# TD_Toolboard_V2.net
KiCad netlist of a schematic drawn in EAGLE
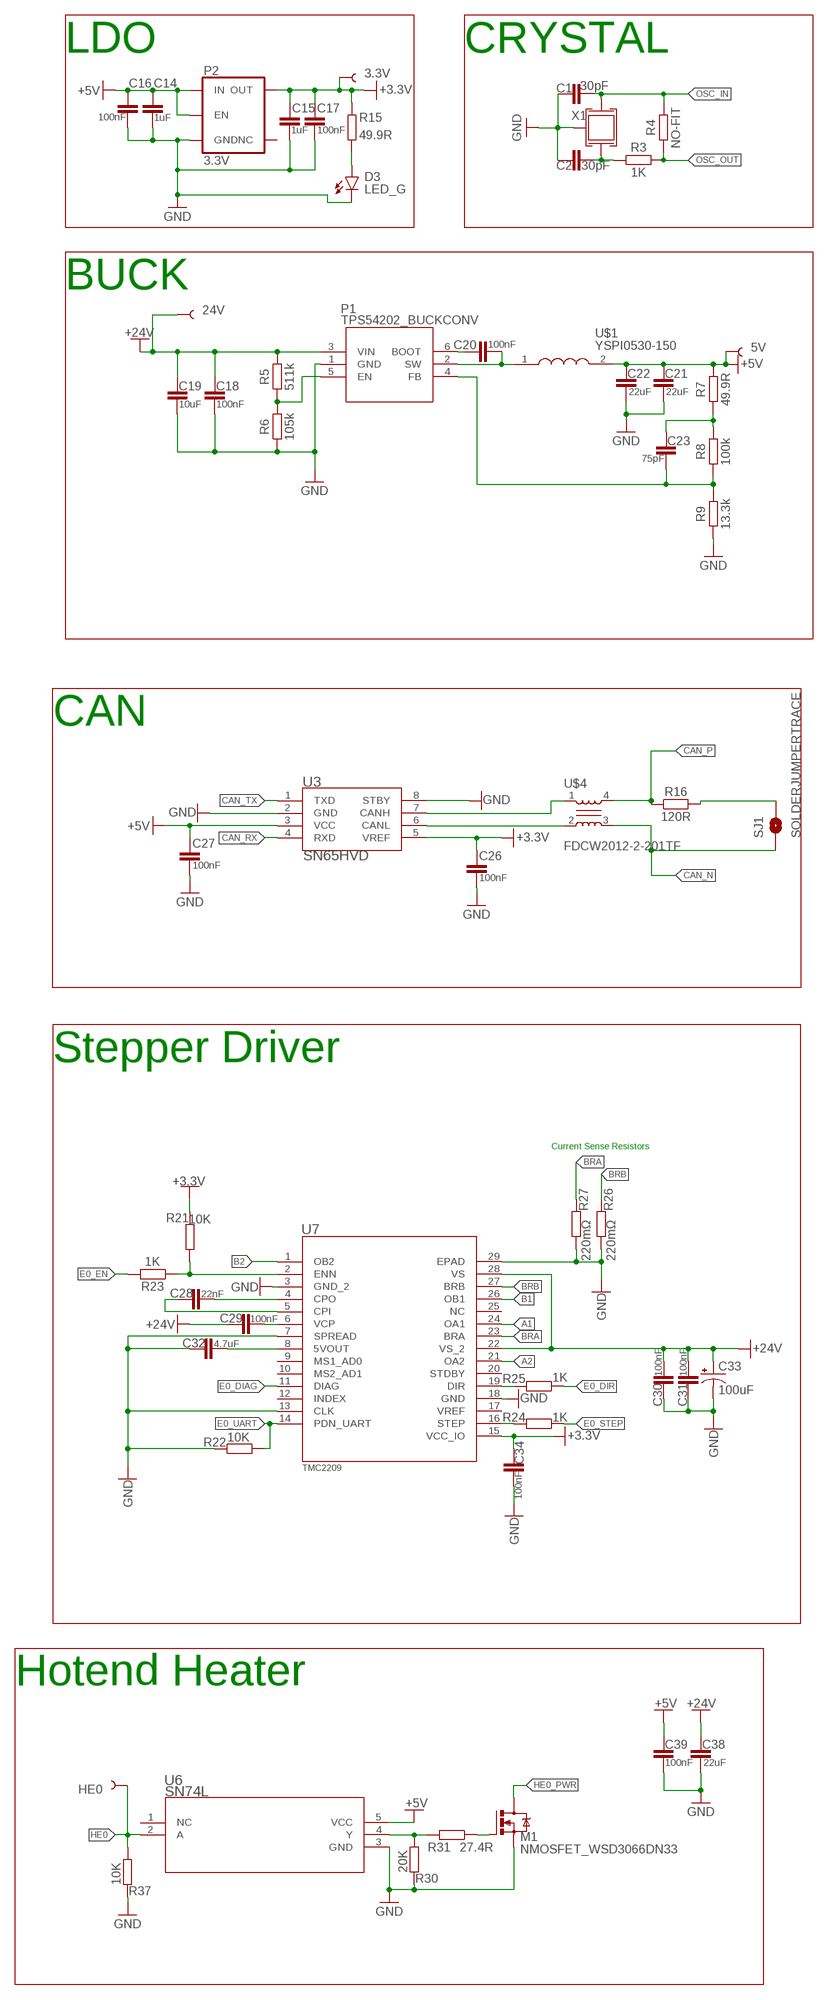
[diagram p0: schematic, sheet 1, part 1 of 2]
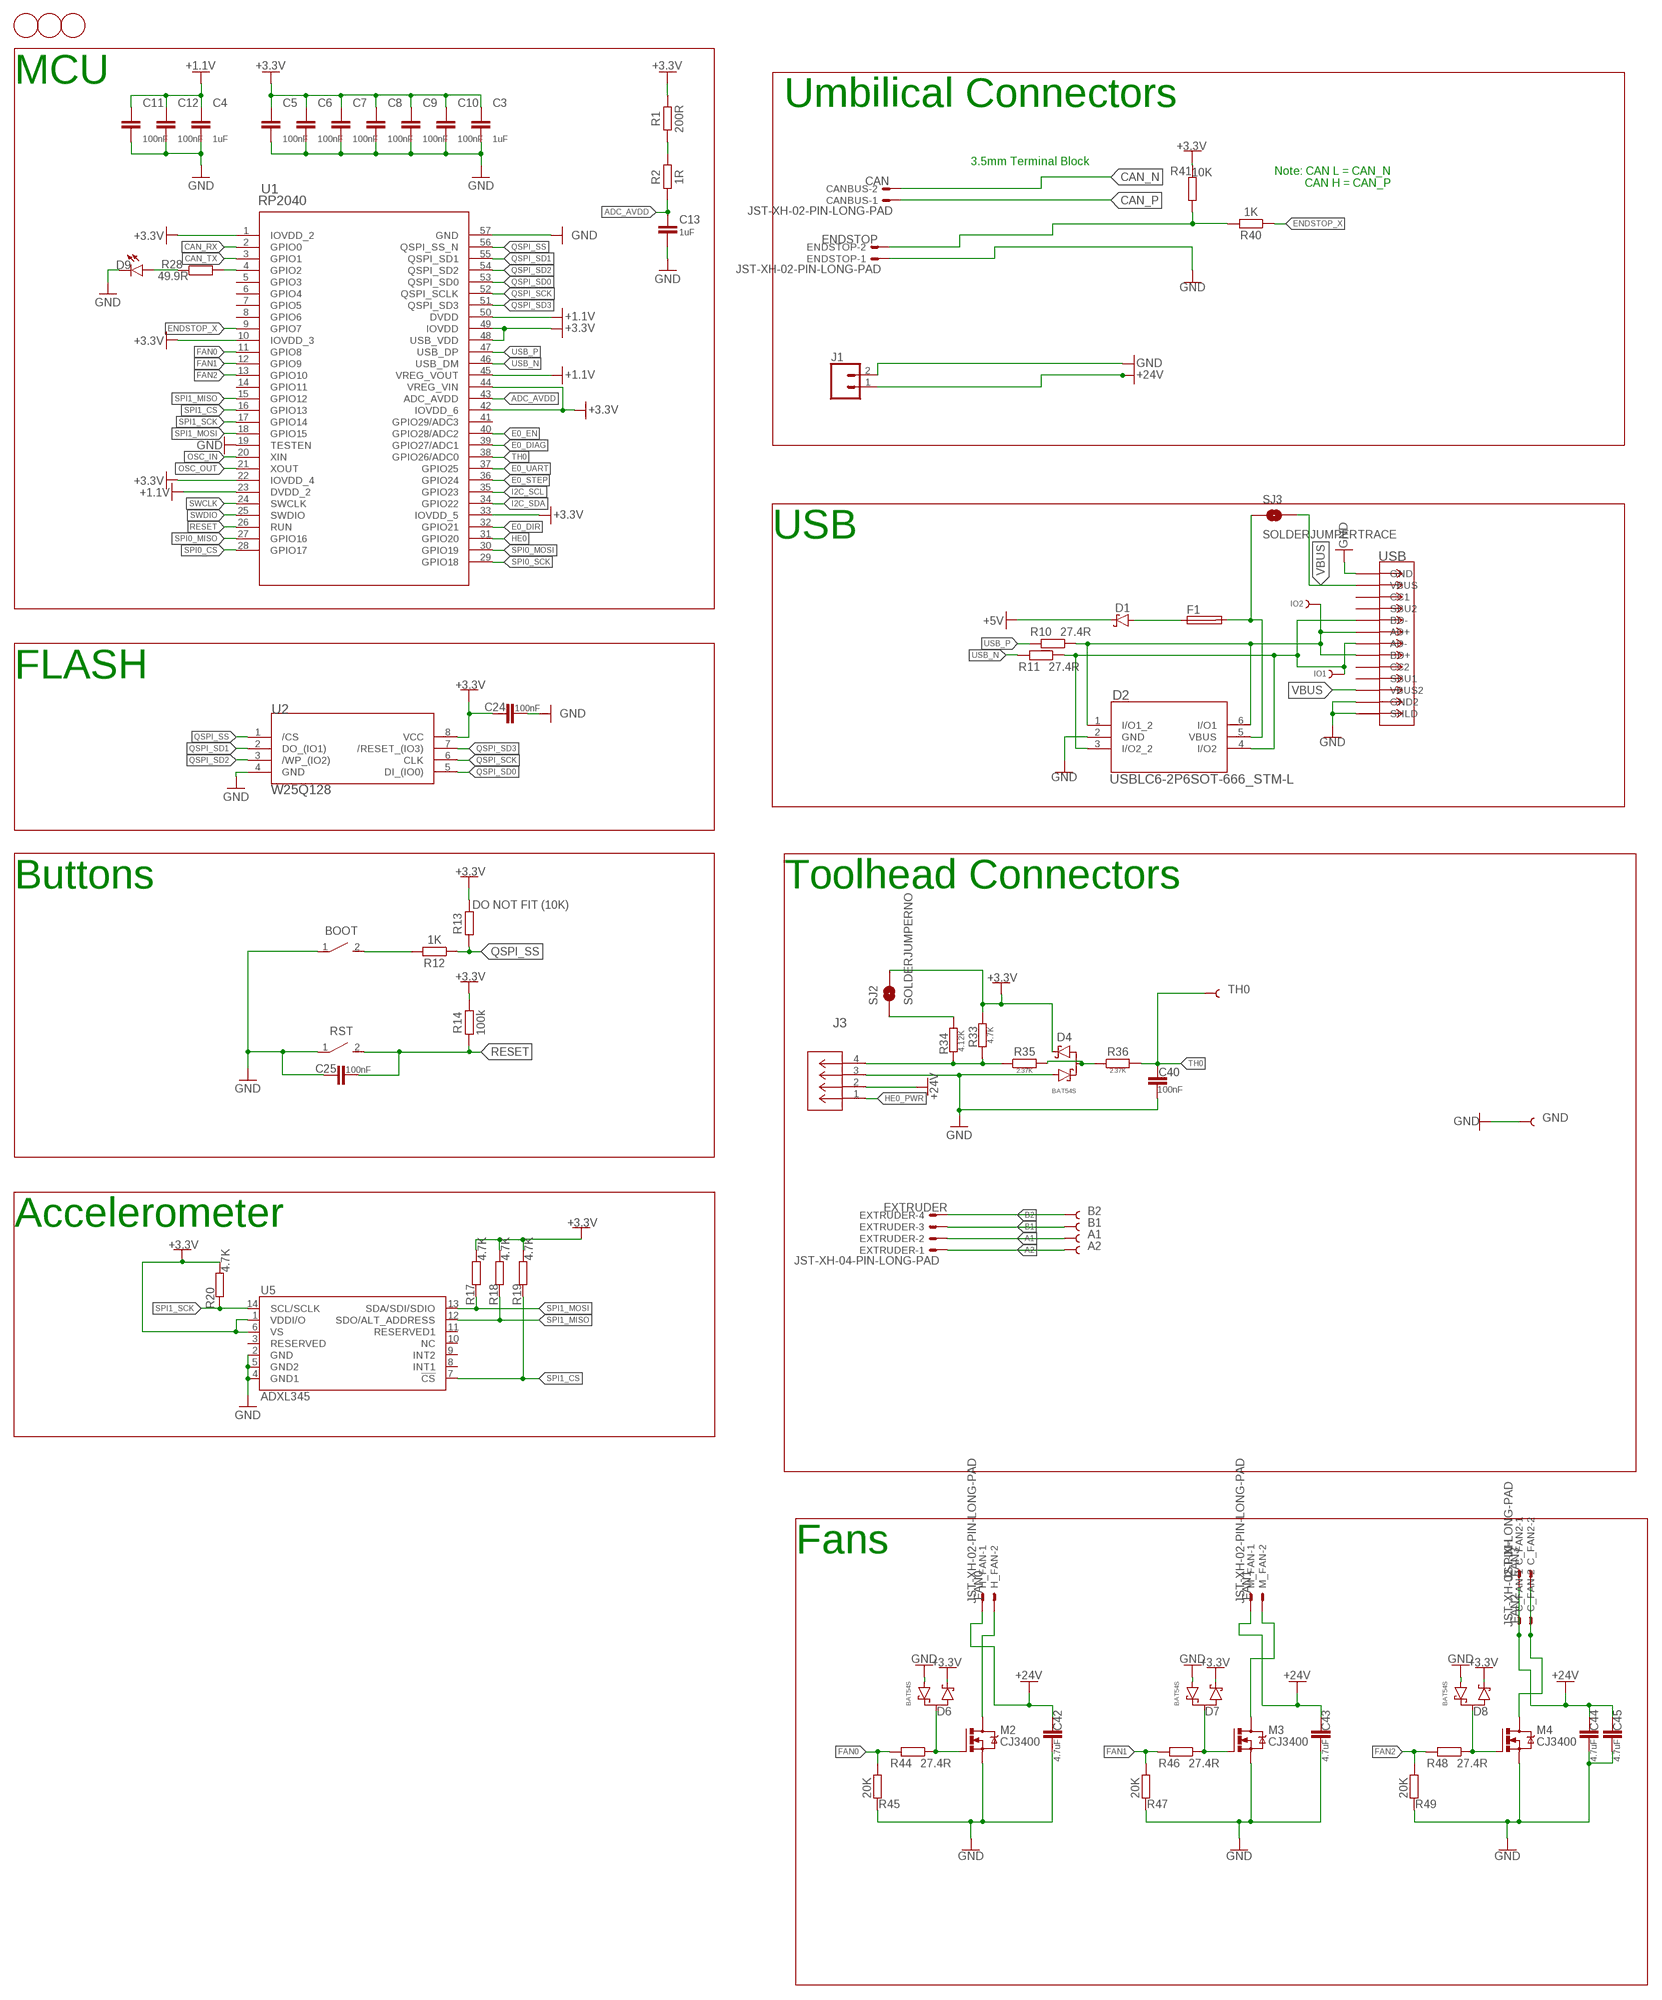
[diagram p1: schematic, sheet 1, part 2 of 2]

(export (version "E")
  (design (tool "Eeschema 10.0.6"))
  (components
    (comp (ref "3.3V")
      (value "TEST-POINT3X4")
      (footprint "eagle-import:PAD.03X.04")
      (libsource (lib "eagle-import") (part "TEST-POINT3X4"))
    )
    (comp (ref "5V")
      (value "TEST-POINT3X4")
      (footprint "eagle-import:PAD.03X.04")
      (libsource (lib "eagle-import") (part "TEST-POINT3X4"))
    )
    (comp (ref "24V")
      (value "TEST-POINT3X4")
      (footprint "eagle-import:PAD.03X.04")
      (libsource (lib "eagle-import") (part "TEST-POINT3X4"))
    )
    (comp (ref "A1")
      (value "TEST-POINT3X4")
      (footprint "eagle-import:PAD.03X.04")
      (libsource (lib "eagle-import") (part "TEST-POINT3X4"))
    )
    (comp (ref "A2")
      (value "TEST-POINT3X4")
      (footprint "eagle-import:PAD.03X.04")
      (libsource (lib "eagle-import") (part "TEST-POINT3X4"))
    )
    (comp (ref "B1")
      (value "TEST-POINT3X4")
      (footprint "eagle-import:PAD.03X.04")
      (libsource (lib "eagle-import") (part "TEST-POINT3X4"))
    )
    (comp (ref "B2")
      (value "TEST-POINT3X4")
      (footprint "eagle-import:PAD.03X.04")
      (libsource (lib "eagle-import") (part "TEST-POINT3X4"))
    )
    (comp (ref "BOOT")
      (value "B3U-1000P(M)-B")
      (footprint "eagle-import:B3U-1000P(M)-B")
      (fields (field (name "MANUFACTURER") "OMRON"))
      (libsource (lib "eagle-import") (part "B3U-X0001000P(M)-BB3U-1000P(M)-B"))
    )
    (comp (ref "C1")
      (value "30pF")
      (footprint "eagle-import:CAPC1005X60")
      (libsource (lib "eagle-import") (part "CCHIP-0402(1005-METRIC)_"))
    )
    (comp (ref "C2")
      (value "30pF")
      (footprint "eagle-import:CAPC1005X60")
      (libsource (lib "eagle-import") (part "CCHIP-0402(1005-METRIC)_"))
    )
    (comp (ref "C3")
      (value "1uF")
      (footprint "eagle-import:CAPC1005X60")
      (libsource (lib "eagle-import") (part "CCHIP-0402(1005-METRIC)_"))
    )
    (comp (ref "C4")
      (value "1uF")
      (footprint "eagle-import:CAPC1005X60")
      (libsource (lib "eagle-import") (part "CCHIP-0402(1005-METRIC)_"))
    )
    (comp (ref "C5")
      (value "100nF")
      (footprint "eagle-import:CAPC1005X60")
      (libsource (lib "eagle-import") (part "CCHIP-0402(1005-METRIC)_"))
    )
    (comp (ref "C6")
      (value "100nF")
      (footprint "eagle-import:CAPC1005X60")
      (libsource (lib "eagle-import") (part "CCHIP-0402(1005-METRIC)_"))
    )
    (comp (ref "C7")
      (value "100nF")
      (footprint "eagle-import:CAPC1005X60")
      (libsource (lib "eagle-import") (part "CCHIP-0402(1005-METRIC)_"))
    )
    (comp (ref "C8")
      (value "100nF")
      (footprint "eagle-import:CAPC1005X60")
      (libsource (lib "eagle-import") (part "CCHIP-0402(1005-METRIC)_"))
    )
    (comp (ref "C9")
      (value "100nF")
      (footprint "eagle-import:CAPC1005X60")
      (libsource (lib "eagle-import") (part "CCHIP-0402(1005-METRIC)_"))
    )
    (comp (ref "C10")
      (value "100nF")
      (footprint "eagle-import:CAPC1005X60")
      (libsource (lib "eagle-import") (part "CCHIP-0402(1005-METRIC)_"))
    )
    (comp (ref "C11")
      (value "100nF")
      (footprint "eagle-import:CAPC1005X60")
      (libsource (lib "eagle-import") (part "CCHIP-0402(1005-METRIC)_"))
    )
    (comp (ref "C12")
      (value "100nF")
      (footprint "eagle-import:CAPC1005X60")
      (libsource (lib "eagle-import") (part "CCHIP-0402(1005-METRIC)_"))
    )
    (comp (ref "C13")
      (value "1uF")
      (footprint "eagle-import:CAPC1005X60")
      (libsource (lib "eagle-import") (part "CCHIP-0402(1005-METRIC)_"))
    )
    (comp (ref "C14")
      (value "1uF")
      (footprint "eagle-import:CAPC1005X60")
      (libsource (lib "eagle-import") (part "CCHIP-0402(1005-METRIC)_"))
    )
    (comp (ref "C15")
      (value "1uF")
      (footprint "eagle-import:CAPC1005X60")
      (libsource (lib "eagle-import") (part "CCHIP-0402(1005-METRIC)_"))
    )
    (comp (ref "C16")
      (value "100nF")
      (footprint "eagle-import:CAPC1005X60")
      (libsource (lib "eagle-import") (part "CCHIP-0402(1005-METRIC)_"))
    )
    (comp (ref "C17")
      (value "100nF")
      (footprint "eagle-import:CAPC1005X60")
      (libsource (lib "eagle-import") (part "CCHIP-0402(1005-METRIC)_"))
    )
    (comp (ref "C18")
      (value "100nF")
      (footprint "eagle-import:CAPC1005X60")
      (libsource (lib "eagle-import") (part "CCHIP-0402(1005-METRIC)_"))
    )
    (comp (ref "C19")
      (value "10uF")
      (footprint "eagle-import:CAPC1608X85")
      (libsource (lib "eagle-import") (part "CCHIP-0603(1608-METRIC)_"))
    )
    (comp (ref "C20")
      (value "100nF")
      (footprint "eagle-import:CAPC1005X60")
      (libsource (lib "eagle-import") (part "CCHIP-0402(1005-METRIC)_"))
    )
    (comp (ref "C21")
      (value "22uF")
      (footprint "eagle-import:CAPC2012X110")
      (libsource (lib "eagle-import") (part "CCHIP-0805(2012-METRIC)_"))
    )
    (comp (ref "C22")
      (value "22uF")
      (footprint "eagle-import:CAPC2012X110")
      (libsource (lib "eagle-import") (part "CCHIP-0805(2012-METRIC)_"))
    )
    (comp (ref "C23")
      (value "75pF")
      (footprint "eagle-import:CAPC1005X60")
      (libsource (lib "eagle-import") (part "CCHIP-0402(1005-METRIC)_"))
    )
    (comp (ref "C24")
      (value "100nF")
      (footprint "eagle-import:CAPC1005X60")
      (libsource (lib "eagle-import") (part "CCHIP-0402(1005-METRIC)_"))
    )
    (comp (ref "C25")
      (value "100nF")
      (footprint "eagle-import:CAPC1005X60")
      (libsource (lib "eagle-import") (part "CCHIP-0402(1005-METRIC)_"))
    )
    (comp (ref "C26")
      (value "100nF")
      (footprint "eagle-import:CAPC1005X60")
      (libsource (lib "eagle-import") (part "CCHIP-0402(1005-METRIC)_"))
    )
    (comp (ref "C27")
      (value "100nF")
      (footprint "eagle-import:CAPC1005X60")
      (libsource (lib "eagle-import") (part "CCHIP-0402(1005-METRIC)_"))
    )
    (comp (ref "C28")
      (value "22nF")
      (footprint "eagle-import:CAPC1005X60")
      (libsource (lib "eagle-import") (part "CCHIP-0402(1005-METRIC)_"))
    )
    (comp (ref "C29")
      (value "100nF")
      (footprint "eagle-import:CAPC1005X60")
      (libsource (lib "eagle-import") (part "CCHIP-0402(1005-METRIC)_"))
    )
    (comp (ref "C30")
      (value "100nF")
      (footprint "eagle-import:CAPC1005X60")
      (libsource (lib "eagle-import") (part "CCHIP-0402(1005-METRIC)_"))
    )
    (comp (ref "C31")
      (value "100nF")
      (footprint "eagle-import:CAPC1005X60")
      (libsource (lib "eagle-import") (part "CCHIP-0402(1005-METRIC)_"))
    )
    (comp (ref "C32")
      (value "4.7uF")
      (footprint "eagle-import:CAPC1608X85")
      (libsource (lib "eagle-import") (part "CCHIP-0603(1608-METRIC)_"))
    )
    (comp (ref "C33")
      (value "100uF")
      (footprint "eagle-import:PANASONIC_D")
      (libsource (lib "eagle-import") (part "100UF-POLAR-25V-20%(ELEC)"))
    )
    (comp (ref "C34")
      (value "100nF")
      (footprint "eagle-import:CAPC1005X60")
      (libsource (lib "eagle-import") (part "CCHIP-0402(1005-METRIC)_"))
    )
    (comp (ref "C38")
      (value "22uF")
      (footprint "eagle-import:CAPC2012X110")
      (libsource (lib "eagle-import") (part "CCHIP-0805(2012-METRIC)_"))
    )
    (comp (ref "C39")
      (value "100nF")
      (footprint "eagle-import:CAPC1005X60")
      (libsource (lib "eagle-import") (part "CCHIP-0402(1005-METRIC)_"))
    )
    (comp (ref "C40")
      (value "100nF")
      (footprint "eagle-import:CAPC1005X60")
      (libsource (lib "eagle-import") (part "CCHIP-0402(1005-METRIC)_"))
    )
    (comp (ref "C42")
      (value "4.7uF")
      (footprint "eagle-import:CAPC1608X85")
      (libsource (lib "eagle-import") (part "CCHIP-0603(1608-METRIC)_"))
    )
    (comp (ref "C43")
      (value "4.7uF")
      (footprint "eagle-import:CAPC1608X85")
      (libsource (lib "eagle-import") (part "CCHIP-0603(1608-METRIC)_"))
    )
    (comp (ref "C44")
      (value "4.7uF")
      (footprint "eagle-import:CAPC1608X85")
      (libsource (lib "eagle-import") (part "CCHIP-0603(1608-METRIC)_"))
    )
    (comp (ref "C45")
      (value "4.7uF")
      (footprint "eagle-import:CAPC1608X85")
      (libsource (lib "eagle-import") (part "CCHIP-0603(1608-METRIC)_"))
    )
    (comp (ref "CANBUS")
      (value "JST-XH-02-PIN-LONG-PAD")
      (footprint "eagle-import:JST-XH-02-PACKAGE-LONG-PAD")
      (libsource (lib "eagle-import") (part "JST-XH-02-PIN-LONG-PAD"))
    )
    (comp (ref "C_FAN")
      (value "JST-XH-02-PIN-LONG-PAD")
      (footprint "eagle-import:JST-XH-02-PACKAGE-LONG-PAD")
      (libsource (lib "eagle-import") (part "JST-XH-02-PIN-LONG-PAD"))
    )
    (comp (ref "C_FAN2")
      (value "JST-XH")
      (footprint "eagle-import:JST-XH-02-PACKAGE-LONG-PAD")
      (libsource (lib "eagle-import") (part "JST-XH-02-PIN-LONG-PAD"))
    )
    (comp (ref "D1")
      (value "MBR0520LT1G")
      (footprint "eagle-import:SODFL3718X115")
      (fields (field (name "MANUFACTURER") "ON Semiconductor"))
      (libsource (lib "eagle-import") (part "SCHOTTKY_DO-219MBR0520LT1G"))
    )
    (comp (ref "D2")
      (value "USBLC6-2P6SOT-666_STM-L")
      (footprint "eagle-import:SOT-666_STM-L")
      (fields
        (field (name "MANUFACTURER_PART_NUMBER") "USBLC6-2P6")
        (field (name "COPYRIGHT") "Copyright (C) 2023 Ultra Librarian. All rights reserved.")
      )
      (libsource (lib "eagle-import") (part "USBLC6-2P6SOT-666_STM-L"))
    )
    (comp (ref "D3")
      (value "LED_G")
      (footprint "eagle-import:LEDC1608X35N_FLAT-G")
      (libsource (lib "eagle-import") (part "CHIP-FLAT-G_0603-0.35MM"))
    )
    (comp (ref "D4")
      (value "BAT54S")
      (footprint "eagle-import:SOT23")
      (libsource (lib "eagle-import") (part "BAT54S"))
    )
    (comp (ref "D6")
      (value "BAT54S")
      (footprint "eagle-import:SOT23")
      (libsource (lib "eagle-import") (part "BAT54S"))
    )
    (comp (ref "D7")
      (value "BAT54S")
      (footprint "eagle-import:SOT23")
      (libsource (lib "eagle-import") (part "BAT54S"))
    )
    (comp (ref "D8")
      (value "BAT54S")
      (footprint "eagle-import:SOT23")
      (libsource (lib "eagle-import") (part "BAT54S"))
    )
    (comp (ref "D9")
      (value "LED_G")
      (footprint "eagle-import:LED3MM")
      (libsource (lib "eagle-import") (part "LED3MM"))
    )
    (comp (ref "ENDSTOP")
      (value "JST-XH-02-PIN-LONG-PAD")
      (footprint "eagle-import:JST-XH-02-PACKAGE-LONG-PAD")
      (libsource (lib "eagle-import") (part "JST-XH-02-PIN-LONG-PAD"))
    )
    (comp (ref "EXTRUDER")
      (value "JST-XH-04-PIN-LONG-PAD")
      (footprint "eagle-import:JST-XH-04-PACKAGE-LONG-PAD")
      (libsource (lib "eagle-import") (part "JST-XH-04-PIN-LONG-PAD"))
    )
    (comp (ref "F1")
      (value "FUSE_CHIP-0603(1608-METRIC)")
      (footprint "eagle-import:FUSC1608X60N")
      (libsource (lib "eagle-import") (part "FUSECHIP-0603(1608-METRIC)_"))
    )
    (comp (ref "FD4")
      (value "FIDUCIAL")
      (footprint "eagle-import:FIDUCIAL_1MM")
      (libsource (lib "eagle-import") (part "FIDUCIAL"))
    )
    (comp (ref "FD5")
      (value "FIDUCIAL")
      (footprint "eagle-import:FIDUCIAL_1MM")
      (libsource (lib "eagle-import") (part "FIDUCIAL"))
    )
    (comp (ref "FD6")
      (value "FIDUCIAL")
      (footprint "eagle-import:FIDUCIAL_1MM")
      (libsource (lib "eagle-import") (part "FIDUCIAL"))
    )
    (comp (ref "GND")
      (value "TEST-POINT3X4")
      (footprint "eagle-import:PAD.03X.04")
      (libsource (lib "eagle-import") (part "TEST-POINT3X4"))
    )
    (comp (ref "HE0")
      (value "TEST-POINT3X4")
      (footprint "eagle-import:PAD.03X.04")
      (libsource (lib "eagle-import") (part "TEST-POINT3X4"))
    )
    (comp (ref "H_FAN")
      (value "JST-XH-02-PIN-LONG-PAD")
      (footprint "eagle-import:JST-XH-02-PACKAGE-LONG-PAD")
      (libsource (lib "eagle-import") (part "JST-XH-02-PIN-LONG-PAD"))
    )
    (comp (ref "IO1")
      (value "TEST-POINT3")
      (footprint "eagle-import:PAD.03X.03")
      (libsource (lib "eagle-import") (part "TEST-POINT3"))
    )
    (comp (ref "IO2")
      (value "TEST-POINT3")
      (footprint "eagle-import:PAD.03X.03")
      (libsource (lib "eagle-import") (part "TEST-POINT3"))
    )
    (comp (ref "J1")
      (value "CONN_023.5MM")
      (footprint "eagle-import:SCREWTERMINAL-3.5MM-2")
      (libsource (lib "eagle-import") (part "CONN_023.5MM"))
    )
    (comp (ref "J3")
      (value "JST-MICROFIT")
      (footprint "eagle-import:CON_430450400_MOL")
      (fields
        (field (name "MANUFACTURER_PART_NUMBER") "430450400")
        (field (name "COPYRIGHT") "Copyright (C) 2023 Ultra Librarian. All rights reserved.")
      )
      (libsource (lib "eagle-import") (part "430450400CON_430450400_MOL"))
    )
    (comp (ref "M1")
      (value "NMOSFET_WSD3066DN33")
      (footprint "eagle-import:NMOSFET_WSD3066DN33")
      (libsource (lib "eagle-import") (part "NMOSFET_WSD3066DN33"))
    )
    (comp (ref "M2")
      (value "CJ3400")
      (footprint "eagle-import:SOT23")
      (fields (field (name "MANUFACTURER") "ON Semiconductor") (field (name "MPN") "BSS123L"))
      (libsource (lib "eagle-import") (part "NMOSFET__SOT23-GSDBSS123"))
    )
    (comp (ref "M3")
      (value "CJ3400")
      (footprint "eagle-import:SOT23")
      (fields (field (name "MANUFACTURER") "ON Semiconductor") (field (name "MPN") "BSS123L"))
      (libsource (lib "eagle-import") (part "NMOSFET__SOT23-GSDBSS123"))
    )
    (comp (ref "M4")
      (value "CJ3400")
      (footprint "eagle-import:SOT23")
      (fields (field (name "MANUFACTURER") "ON Semiconductor") (field (name "MPN") "BSS123L"))
      (libsource (lib "eagle-import") (part "NMOSFET__SOT23-GSDBSS123"))
    )
    (comp (ref "M_FAN")
      (value "JST-XH-02-PIN-LONG-PAD")
      (footprint "eagle-import:JST-XH-02-PACKAGE-LONG-PAD")
      (libsource (lib "eagle-import") (part "JST-XH-02-PIN-LONG-PAD"))
    )
    (comp (ref "P1")
      (value "TPS54202_BUCKCONV")
      (footprint "eagle-import:SOT-23-6")
      (libsource (lib "eagle-import") (part "TPS54202_BUCKCONV"))
    )
    (comp (ref "P2")
      (value "3.3V")
      (footprint "eagle-import:SOT23-5")
      (libsource (lib "eagle-import") (part "V_REG_AP2112K-3.3V"))
    )
    (comp (ref "R1")
      (value "200R")
      (footprint "eagle-import:RESC1005X40")
      (libsource (lib "eagle-import") (part "RCHIP-0402(1005-METRIC)_"))
    )
    (comp (ref "R2")
      (value "1R")
      (footprint "eagle-import:RESC1005X40")
      (libsource (lib "eagle-import") (part "RCHIP-0402(1005-METRIC)_"))
    )
    (comp (ref "R3")
      (value "1K")
      (footprint "eagle-import:RESC1005X40")
      (libsource (lib "eagle-import") (part "RCHIP-0402(1005-METRIC)_"))
    )
    (comp (ref "R4")
      (value "NO-FIT")
      (footprint "eagle-import:RESC1005X40")
      (libsource (lib "eagle-import") (part "RCHIP-0402(1005-METRIC)_"))
    )
    (comp (ref "R5")
      (value "511k")
      (footprint "eagle-import:RESC1005X40")
      (libsource (lib "eagle-import") (part "RCHIP-0402(1005-METRIC)_"))
    )
    (comp (ref "R6")
      (value "105k")
      (footprint "eagle-import:RESC1005X40")
      (libsource (lib "eagle-import") (part "RCHIP-0402(1005-METRIC)_"))
    )
    (comp (ref "R7")
      (value "49.9R")
      (footprint "eagle-import:RESC1005X40")
      (libsource (lib "eagle-import") (part "RCHIP-0402(1005-METRIC)_"))
    )
    (comp (ref "R8")
      (value "100k")
      (footprint "eagle-import:RESC1005X40")
      (libsource (lib "eagle-import") (part "RCHIP-0402(1005-METRIC)_"))
    )
    (comp (ref "R9")
      (value "13.3k")
      (footprint "eagle-import:RESC1005X40")
      (libsource (lib "eagle-import") (part "RCHIP-0402(1005-METRIC)_"))
    )
    (comp (ref "R10")
      (value "27.4R")
      (footprint "eagle-import:RESC1005X40")
      (libsource (lib "eagle-import") (part "RCHIP-0402(1005-METRIC)_"))
    )
    (comp (ref "R11")
      (value "27.4R")
      (footprint "eagle-import:RESC1005X40")
      (libsource (lib "eagle-import") (part "RCHIP-0402(1005-METRIC)_"))
    )
    (comp (ref "R12")
      (value "1K")
      (footprint "eagle-import:RESC1005X40")
      (libsource (lib "eagle-import") (part "RCHIP-0402(1005-METRIC)_"))
    )
    (comp (ref "R13")
      (value "DO NOT FIT (10K)")
      (footprint "eagle-import:RESC1005X40")
      (libsource (lib "eagle-import") (part "RCHIP-0402(1005-METRIC)_"))
    )
    (comp (ref "R14")
      (value "100k")
      (footprint "eagle-import:RESC1005X40")
      (libsource (lib "eagle-import") (part "RCHIP-0402(1005-METRIC)_"))
    )
    (comp (ref "R15")
      (value "49.9R")
      (footprint "eagle-import:RESC1005X40")
      (libsource (lib "eagle-import") (part "RCHIP-0402(1005-METRIC)_"))
    )
    (comp (ref "R16")
      (value "120R")
      (footprint "eagle-import:RESC1005X40")
      (libsource (lib "eagle-import") (part "RCHIP-0402(1005-METRIC)_"))
    )
    (comp (ref "R17")
      (value "4.7K")
      (footprint "eagle-import:RESC1005X40")
      (libsource (lib "eagle-import") (part "RCHIP-0402(1005-METRIC)_"))
    )
    (comp (ref "R18")
      (value "4.7K")
      (footprint "eagle-import:RESC1005X40")
      (libsource (lib "eagle-import") (part "RCHIP-0402(1005-METRIC)_"))
    )
    (comp (ref "R19")
      (value "4.7K")
      (footprint "eagle-import:RESC1005X40")
      (libsource (lib "eagle-import") (part "RCHIP-0402(1005-METRIC)_"))
    )
    (comp (ref "R20")
      (value "4.7K")
      (footprint "eagle-import:RESC1005X40")
      (libsource (lib "eagle-import") (part "RCHIP-0402(1005-METRIC)_"))
    )
    (comp (ref "R21")
      (value "10K")
      (footprint "eagle-import:RESC1005X40")
      (libsource (lib "eagle-import") (part "RCHIP-0402(1005-METRIC)_"))
    )
    (comp (ref "R22")
      (value "10K")
      (footprint "eagle-import:RESC1005X40")
      (libsource (lib "eagle-import") (part "RCHIP-0402(1005-METRIC)_"))
    )
    (comp (ref "R23")
      (value "1K")
      (footprint "eagle-import:RESC1005X40")
      (libsource (lib "eagle-import") (part "RCHIP-0402(1005-METRIC)_"))
    )
    (comp (ref "R24")
      (value "1K")
      (footprint "eagle-import:RESC1005X40")
      (libsource (lib "eagle-import") (part "RCHIP-0402(1005-METRIC)_"))
    )
    (comp (ref "R25")
      (value "1K")
      (footprint "eagle-import:RESC1005X40")
      (libsource (lib "eagle-import") (part "RCHIP-0402(1005-METRIC)_"))
    )
    (comp (ref "R26")
      (value "220mΩ")
      (footprint "eagle-import:RESC1005X40")
      (libsource (lib "eagle-import") (part "RCHIP-0402(1005-METRIC)_"))
    )
    (comp (ref "R27")
      (value "220mΩ")
      (footprint "eagle-import:RESC1005X40")
      (libsource (lib "eagle-import") (part "RCHIP-0402(1005-METRIC)_"))
    )
    (comp (ref "R28")
      (value "49.9R")
      (footprint "eagle-import:RESC1005X40")
      (libsource (lib "eagle-import") (part "RCHIP-0402(1005-METRIC)_"))
    )
    (comp (ref "R30")
      (value "20K")
      (footprint "eagle-import:RESC1005X40")
      (libsource (lib "eagle-import") (part "RCHIP-0402(1005-METRIC)_"))
    )
    (comp (ref "R31")
      (value "27.4R")
      (footprint "eagle-import:RESC1005X40")
      (libsource (lib "eagle-import") (part "RCHIP-0402(1005-METRIC)_"))
    )
    (comp (ref "R33")
      (value "4.7K")
      (footprint "eagle-import:RESC1005X40")
      (libsource (lib "eagle-import") (part "RCHIP-0402(1005-METRIC)_"))
    )
    (comp (ref "R34")
      (value "4.12K")
      (footprint "eagle-import:RESC1005X40")
      (libsource (lib "eagle-import") (part "RCHIP-0402(1005-METRIC)_"))
    )
    (comp (ref "R35")
      (value "2.37K")
      (footprint "eagle-import:RESC1005X40")
      (libsource (lib "eagle-import") (part "RCHIP-0402(1005-METRIC)_"))
    )
    (comp (ref "R36")
      (value "2.37K")
      (footprint "eagle-import:RESC1005X40")
      (libsource (lib "eagle-import") (part "RCHIP-0402(1005-METRIC)_"))
    )
    (comp (ref "R37")
      (value "10K")
      (footprint "eagle-import:RESC1005X40")
      (libsource (lib "eagle-import") (part "RCHIP-0402(1005-METRIC)_"))
    )
    (comp (ref "R40")
      (value "1K")
      (footprint "eagle-import:RESC1005X40")
      (libsource (lib "eagle-import") (part "RCHIP-0402(1005-METRIC)_"))
    )
    (comp (ref "R41")
      (value "10K")
      (footprint "eagle-import:RESC1005X40")
      (libsource (lib "eagle-import") (part "RCHIP-0402(1005-METRIC)_"))
    )
    (comp (ref "R44")
      (value "27.4R")
      (footprint "eagle-import:RESC1005X40")
      (libsource (lib "eagle-import") (part "RCHIP-0402(1005-METRIC)_"))
    )
    (comp (ref "R45")
      (value "20K")
      (footprint "eagle-import:RESC1005X40")
      (libsource (lib "eagle-import") (part "RCHIP-0402(1005-METRIC)_"))
    )
    (comp (ref "R46")
      (value "27.4R")
      (footprint "eagle-import:RESC1005X40")
      (libsource (lib "eagle-import") (part "RCHIP-0402(1005-METRIC)_"))
    )
    (comp (ref "R47")
      (value "20K")
      (footprint "eagle-import:RESC1005X40")
      (libsource (lib "eagle-import") (part "RCHIP-0402(1005-METRIC)_"))
    )
    (comp (ref "R48")
      (value "27.4R")
      (footprint "eagle-import:RESC1005X40")
      (libsource (lib "eagle-import") (part "RCHIP-0402(1005-METRIC)_"))
    )
    (comp (ref "R49")
      (value "20K")
      (footprint "eagle-import:RESC1005X40")
      (libsource (lib "eagle-import") (part "RCHIP-0402(1005-METRIC)_"))
    )
    (comp (ref "RST")
      (value "B3U-1000P(M)-B")
      (footprint "eagle-import:B3U-1000P(M)-B")
      (fields (field (name "MANUFACTURER") "OMRON"))
      (libsource (lib "eagle-import") (part "B3U-X0001000P(M)-BB3U-1000P(M)-B"))
    )
    (comp (ref "SJ1")
      (value "SOLDERJUMPERTRACE")
      (footprint "eagle-import:SJ_2S-TRACE")
      (libsource (lib "eagle-import") (part "SOLDERJUMPERTRACE"))
    )
    (comp (ref "SJ2")
      (value "SOLDERJUMPERNO")
      (footprint "eagle-import:SJ_2S-NO")
      (libsource (lib "eagle-import") (part "SOLDERJUMPERNO"))
    )
    (comp (ref "SJ3")
      (value "SOLDERJUMPERTRACE")
      (footprint "eagle-import:SJ_2S-TRACE")
      (libsource (lib "eagle-import") (part "SOLDERJUMPERTRACE"))
    )
    (comp (ref "TH0")
      (value "TEST-POINT3X4")
      (footprint "eagle-import:PAD.03X.04")
      (libsource (lib "eagle-import") (part "TEST-POINT3X4"))
    )
    (comp (ref "U$1")
      (value "YSPI0530-150")
      (footprint "eagle-import:YSPI0530-150")
      (libsource (lib "eagle-import") (part "YSPI0530-150"))
    )
    (comp (ref "U$4")
      (value "FDCW2012-2-201TF")
      (footprint "eagle-import:FDCW2012-2-201TF")
      (libsource (lib "eagle-import") (part "FDCW2012-2-201TF"))
    )
    (comp (ref "U1")
      (value "RP2040")
      (footprint "eagle-import:IC57_RP2040-L")
      (fields (field (name "COPYRIGHT") "Copyright (C) 2023 Ultra Librarian. All rights reserved."))
      (libsource (lib "eagle-import") (part "RP2040IC57_RP2040-L"))
    )
    (comp (ref "U2")
      (value "W25Q128")
      (footprint "eagle-import:SOIC_128JVSIQ_WIN-L")
      (fields
        (field (name "MANUFACTURER_PART_NUMBER") "W25Q128JVSIQ")
        (field (name "COPYRIGHT") "Copyright (C) 2023 Ultra Librarian. All rights reserved.")
      )
      (libsource (lib "eagle-import") (part "W25Q128JVSIQSOIC_128JVSIQ_WIN-L"))
    )
    (comp (ref "U3")
      (value "SN65HVD")
      (footprint "eagle-import:D8-L")
      (fields
        (field (name "MANUFACTURER_PART_NUMBER") "SN65HVD1050DR")
        (field (name "COPYRIGHT") "Copyright (C) 2023 Ultra Librarian. All rights reserved.")
      )
      (libsource (lib "eagle-import") (part "SN65HVD1050DRD8-L"))
    )
    (comp (ref "U5")
      (value "ADXL345")
      (footprint "eagle-import:ADXL345_LGA14")
      (fields (field (name "MANUFACTURER") "ANALOG DEVICES") (field (name "MPN") "ADXL345BCCZ-RL"))
      (libsource (lib "eagle-import") (part "ADXL345BCCZ-RL"))
    )
    (comp (ref "U6")
      (value "SN74L")
      (footprint "eagle-import:DBV5-L")
      (fields
        (field (name "MANUFACTURER_PART_NUMBER") "SN74LVC1G17DBVR")
        (field (name "COPYRIGHT") "Copyright (C) 2023 Ultra Librarian. All rights reserved.")
      )
      (libsource (lib "eagle-import") (part "SN74LVC1G17DBVRDBV5-L"))
    )
    (comp (ref "U7")
      (value "TMC2209")
      (footprint "eagle-import:QFN28_5X5_3X8_EPAD_TRI")
      (fields
        (field (name "MANUFACTURER_PART_NUMBER") "TMC2209-LA-T")
        (field (name "COPYRIGHT") "Copyright (C) 2023 Ultra Librarian. All rights reserved.")
      )
      (libsource (lib "eagle-import") (part "TMC2209-LA-TQFN28_5X5_3X8_EPAD_TRI"))
    )
    (comp (ref "USB")
      (value "USB-C(KH-TYPE-C-16P)")
      (footprint "eagle-import:CONN12_KH-TYPE-C-16P")
      (fields
        (field (name "MANUFACTURER_PART_NUMBER") "DX07S016JA1R1500")
        (field (name "VENDOR") "LCSC")
        (field (name "COPYRIGHT") "Copyright (C) 2018 Accelerated Designs. All rights reserved")
        (field (name "SOURCELIBRARY") "JAE_Electronics_2020-03-30")
      )
      (libsource (lib "eagle-import") (part "USB-C(KH-TYPE-C-16P)"))
    )
    (comp (ref "X1")
      (value "CRYSTAL_TAXM12M4RLBDDT2T_3225")
      (footprint "eagle-import:CRYSTAL_3225")
      (libsource (lib "eagle-import") (part "CRYSTAL_TAXM12M4RLBDDT2T_3225"))
    )
  )
  (nets
    (net (code "1") (name "+1.1V") (class "Default")
      (node (ref "C11") (pin "1") (pinfunction "1_1") (pintype "passive"))
      (node (ref "C12") (pin "1") (pinfunction "1_1") (pintype "passive"))
      (node (ref "C4") (pin "1") (pinfunction "1_1") (pintype "passive"))
      (node (ref "U1") (pin "23") (pinfunction "DVDD_2_23") (pintype "power_in"))
      (node (ref "U1") (pin "45") (pinfunction "VREG_VOUT_45") (pintype "output"))
      (node (ref "U1") (pin "50") (pinfunction "DVDD_50") (pintype "power_in"))
    )
    (net (code "2") (name "+3.3V") (class "Default")
      (node (ref "3.3V") (pin "P$1") (pinfunction "1_P$1") (pintype "bidirectional"))
      (node (ref "C10") (pin "1") (pinfunction "1_1") (pintype "passive"))
      (node (ref "C15") (pin "1") (pinfunction "1_1") (pintype "passive"))
      (node (ref "C17") (pin "1") (pinfunction "1_1") (pintype "passive"))
      (node (ref "C24") (pin "1") (pinfunction "1_1") (pintype "passive"))
      (node (ref "C26") (pin "1") (pinfunction "1_1") (pintype "passive"))
      (node (ref "C3") (pin "1") (pinfunction "1_1") (pintype "passive"))
      (node (ref "C34") (pin "1") (pinfunction "1_1") (pintype "passive"))
      (node (ref "C5") (pin "1") (pinfunction "1_1") (pintype "passive"))
      (node (ref "C6") (pin "1") (pinfunction "1_1") (pintype "passive"))
      (node (ref "C7") (pin "1") (pinfunction "1_1") (pintype "passive"))
      (node (ref "C8") (pin "1") (pinfunction "1_1") (pintype "passive"))
      (node (ref "C9") (pin "1") (pinfunction "1_1") (pintype "passive"))
      (node (ref "D4") (pin "2") (pinfunction "2_2") (pintype "passive"))
      (node (ref "D6") (pin "2") (pinfunction "2_2") (pintype "passive"))
      (node (ref "D7") (pin "2") (pinfunction "2_2") (pintype "passive"))
      (node (ref "D8") (pin "2") (pinfunction "2_2") (pintype "passive"))
      (node (ref "P2") (pin "5") (pinfunction "OUT_5") (pintype "passive"))
      (node (ref "R1") (pin "2") (pinfunction "2_2") (pintype "passive"))
      (node (ref "R13") (pin "2") (pinfunction "2_2") (pintype "passive"))
      (node (ref "R14") (pin "2") (pinfunction "2_2") (pintype "passive"))
      (node (ref "R15") (pin "2") (pinfunction "2_2") (pintype "passive"))
      (node (ref "R17") (pin "2") (pinfunction "2_2") (pintype "passive"))
      (node (ref "R18") (pin "2") (pinfunction "2_2") (pintype "passive"))
      (node (ref "R19") (pin "2") (pinfunction "2_2") (pintype "passive"))
      (node (ref "R20") (pin "2") (pinfunction "2_2") (pintype "passive"))
      (node (ref "R21") (pin "1") (pinfunction "1_1") (pintype "passive"))
      (node (ref "R33") (pin "2") (pinfunction "2_2") (pintype "passive"))
      (node (ref "R41") (pin "1") (pinfunction "1_1") (pintype "passive"))
      (node (ref "SJ2") (pin "2") (pinfunction "2_2") (pintype "passive"))
      (node (ref "U1") (pin "1") (pinfunction "IOVDD_2_1") (pintype "power_in"))
      (node (ref "U1") (pin "10") (pinfunction "IOVDD_3_10") (pintype "power_in"))
      (node (ref "U1") (pin "22") (pinfunction "IOVDD_4_22") (pintype "power_in"))
      (node (ref "U1") (pin "33") (pinfunction "IOVDD_5_33") (pintype "power_in"))
      (node (ref "U1") (pin "42") (pinfunction "IOVDD_6_42") (pintype "power_in"))
      (node (ref "U1") (pin "44") (pinfunction "VREG_VIN_44") (pintype "passive"))
      (node (ref "U1") (pin "48") (pinfunction "USB_VDD_48") (pintype "power_in"))
      (node (ref "U1") (pin "49") (pinfunction "IOVDD_49") (pintype "power_in"))
      (node (ref "U2") (pin "8") (pinfunction "VCC_8") (pintype "power_in"))
      (node (ref "U3") (pin "5") (pinfunction "VREF_5") (pintype "power_in"))
      (node (ref "U5") (pin "1") (pinfunction "VDDI/O_1") (pintype "bidirectional"))
      (node (ref "U5") (pin "6") (pinfunction "VS_6") (pintype "bidirectional"))
      (node (ref "U7") (pin "15") (pinfunction "VCC_IO_15") (pintype "power_in"))
    )
    (net (code "3") (name "+5V") (class "Default")
      (node (ref "5V") (pin "P$1") (pinfunction "1_P$1") (pintype "bidirectional"))
      (node (ref "C14") (pin "1") (pinfunction "1_1") (pintype "passive"))
      (node (ref "C16") (pin "1") (pinfunction "1_1") (pintype "passive"))
      (node (ref "C21") (pin "1") (pinfunction "1_1") (pintype "passive"))
      (node (ref "C22") (pin "1") (pinfunction "1_1") (pintype "passive"))
      (node (ref "C27") (pin "1") (pinfunction "1_1") (pintype "passive"))
      (node (ref "C39") (pin "1") (pinfunction "1_1") (pintype "passive"))
      (node (ref "D1") (pin "1") (pinfunction "C_1") (pintype "passive"))
      (node (ref "P2") (pin "1") (pinfunction "IN_1") (pintype "input"))
      (node (ref "P2") (pin "3") (pinfunction "EN_3") (pintype "input"))
      (node (ref "R7") (pin "2") (pinfunction "2_2") (pintype "passive"))
      (node (ref "U$1") (pin "2") (pinfunction "2_2") (pintype "bidirectional"))
      (node (ref "U3") (pin "3") (pinfunction "VCC_3") (pintype "power_in"))
      (node (ref "U6") (pin "5") (pinfunction "VCC_5") (pintype "power_in"))
    )
    (net (code "4") (name "+24V") (class "Default")
      (node (ref "24V") (pin "P$1") (pinfunction "1_P$1") (pintype "bidirectional"))
      (node (ref "C18") (pin "1") (pinfunction "1_1") (pintype "passive"))
      (node (ref "C19") (pin "1") (pinfunction "1_1") (pintype "passive"))
      (node (ref "C29") (pin "1") (pinfunction "1_1") (pintype "passive"))
      (node (ref "C30") (pin "2") (pinfunction "2_2") (pintype "passive"))
      (node (ref "C31") (pin "2") (pinfunction "2_2") (pintype "passive"))
      (node (ref "C33") (pin "+") (pinfunction "+_+") (pintype "passive"))
      (node (ref "C38") (pin "1") (pinfunction "1_1") (pintype "passive"))
      (node (ref "C42") (pin "1") (pinfunction "1_1") (pintype "passive"))
      (node (ref "C43") (pin "1") (pinfunction "1_1") (pintype "passive"))
      (node (ref "C44") (pin "1") (pinfunction "1_1") (pintype "passive"))
      (node (ref "C45") (pin "1") (pinfunction "1_1") (pintype "passive"))
      (node (ref "C_FAN") (pin "1") (pinfunction "S_1") (pintype "passive"))
      (node (ref "C_FAN2") (pin "1") (pinfunction "S_1") (pintype "passive"))
      (node (ref "H_FAN") (pin "1") (pinfunction "S_1") (pintype "passive"))
      (node (ref "J1") (pin "1") (pinfunction "1_1") (pintype "passive"))
      (node (ref "J3") (pin "2") (pinfunction "2_2") (pintype "passive"))
      (node (ref "M_FAN") (pin "1") (pinfunction "S_1") (pintype "passive"))
      (node (ref "P1") (pin "3") (pinfunction "VIN_3") (pintype "bidirectional"))
      (node (ref "R5") (pin "2") (pinfunction "2_2") (pintype "passive"))
      (node (ref "U7") (pin "22") (pinfunction "VS_2_22") (pintype "power_in"))
      (node (ref "U7") (pin "28") (pinfunction "VS_28") (pintype "power_in"))
    )
    (net (code "5") (name "A1") (class "Default")
      (node (ref "A1") (pin "P$1") (pinfunction "1_P$1") (pintype "bidirectional"))
      (node (ref "EXTRUDER") (pin "2") (pinfunction "S_2") (pintype "passive"))
      (node (ref "U7") (pin "24") (pinfunction "OA1_24") (pintype "output"))
    )
    (net (code "6") (name "A2") (class "Default")
      (node (ref "A2") (pin "P$1") (pinfunction "1_P$1") (pintype "bidirectional"))
      (node (ref "EXTRUDER") (pin "1") (pinfunction "S_1") (pintype "passive"))
      (node (ref "U7") (pin "21") (pinfunction "OA2_21") (pintype "output"))
    )
    (net (code "7") (name "ADC_AVDD") (class "Default")
      (node (ref "C13") (pin "1") (pinfunction "1_1") (pintype "passive"))
      (node (ref "R2") (pin "1") (pinfunction "1_1") (pintype "passive"))
      (node (ref "U1") (pin "43") (pinfunction "ADC_AVDD_43") (pintype "power_in"))
    )
    (net (code "8") (name "B1") (class "Default")
      (node (ref "B1") (pin "P$1") (pinfunction "1_P$1") (pintype "bidirectional"))
      (node (ref "EXTRUDER") (pin "3") (pinfunction "S_3") (pintype "passive"))
      (node (ref "U7") (pin "26") (pinfunction "OB1_26") (pintype "output"))
    )
    (net (code "9") (name "B2") (class "Default")
      (node (ref "B2") (pin "P$1") (pinfunction "1_P$1") (pintype "bidirectional"))
      (node (ref "EXTRUDER") (pin "4") (pinfunction "S_4") (pintype "passive"))
      (node (ref "U7") (pin "1") (pinfunction "OB2_1") (pintype "output"))
    )
    (net (code "10") (name "BRA") (class "Default")
      (node (ref "R27") (pin "2") (pinfunction "2_2") (pintype "passive"))
      (node (ref "U7") (pin "23") (pinfunction "BRA_23") (pintype "passive"))
    )
    (net (code "11") (name "BRB") (class "Default")
      (node (ref "R26") (pin "2") (pinfunction "2_2") (pintype "passive"))
      (node (ref "U7") (pin "27") (pinfunction "BRB_27") (pintype "passive"))
    )
    (net (code "12") (name "CAN_N") (class "Default")
      (node (ref "CANBUS") (pin "2") (pinfunction "S_2") (pintype "passive"))
      (node (ref "SJ1") (pin "1") (pinfunction "1_1") (pintype "passive"))
      (node (ref "U$4") (pin "3") (pinfunction "3_3") (pintype "passive"))
    )
    (net (code "13") (name "CAN_P") (class "Default")
      (node (ref "CANBUS") (pin "1") (pinfunction "S_1") (pintype "passive"))
      (node (ref "R16") (pin "1") (pinfunction "1_1") (pintype "passive"))
      (node (ref "U$4") (pin "4") (pinfunction "4_4") (pintype "passive"))
    )
    (net (code "14") (name "CAN_RX") (class "Default")
      (node (ref "U1") (pin "2") (pinfunction "GPIO0_2") (pintype "bidirectional"))
      (node (ref "U3") (pin "4") (pinfunction "RXD_4") (pintype "output"))
    )
    (net (code "15") (name "CAN_TX") (class "Default")
      (node (ref "U1") (pin "3") (pinfunction "GPIO1_3") (pintype "bidirectional"))
      (node (ref "U3") (pin "1") (pinfunction "TXD_1") (pintype "input"))
    )
    (net (code "16") (name "E0_DIAG") (class "Default")
      (node (ref "U1") (pin "39") (pinfunction "GPIO27/ADC1_39") (pintype "bidirectional"))
      (node (ref "U7") (pin "11") (pinfunction "DIAG_11") (pintype "output"))
    )
    (net (code "17") (name "E0_DIR") (class "Default")
      (node (ref "R25") (pin "1") (pinfunction "1_1") (pintype "passive"))
      (node (ref "U1") (pin "32") (pinfunction "GPIO21_32") (pintype "bidirectional"))
    )
    (net (code "18") (name "E0_EN") (class "Default")
      (node (ref "R23") (pin "2") (pinfunction "2_2") (pintype "passive"))
      (node (ref "U1") (pin "40") (pinfunction "GPIO28/ADC2_40") (pintype "bidirectional"))
    )
    (net (code "19") (name "E0_STEP") (class "Default")
      (node (ref "R24") (pin "1") (pinfunction "1_1") (pintype "passive"))
      (node (ref "U1") (pin "36") (pinfunction "GPIO24_36") (pintype "bidirectional"))
    )
    (net (code "20") (name "E0_UART") (class "Default")
      (node (ref "R22") (pin "2") (pinfunction "2_2") (pintype "passive"))
      (node (ref "U1") (pin "37") (pinfunction "GPIO25_37") (pintype "bidirectional"))
      (node (ref "U7") (pin "14") (pinfunction "PDN_UART_14") (pintype "bidirectional"))
    )
    (net (code "21") (name "ENDSTOP_X") (class "Default")
      (node (ref "R40") (pin "1") (pinfunction "1_1") (pintype "passive"))
      (node (ref "U1") (pin "9") (pinfunction "GPIO7_9") (pintype "bidirectional"))
    )
    (net (code "22") (name "FAN0") (class "Default")
      (node (ref "R44") (pin "2") (pinfunction "2_2") (pintype "passive"))
      (node (ref "R45") (pin "2") (pinfunction "2_2") (pintype "passive"))
      (node (ref "U1") (pin "11") (pinfunction "GPIO8_11") (pintype "bidirectional"))
    )
    (net (code "23") (name "FAN1") (class "Default")
      (node (ref "R46") (pin "2") (pinfunction "2_2") (pintype "passive"))
      (node (ref "R47") (pin "2") (pinfunction "2_2") (pintype "passive"))
      (node (ref "U1") (pin "12") (pinfunction "GPIO9_12") (pintype "bidirectional"))
    )
    (net (code "24") (name "FAN2") (class "Default")
      (node (ref "R48") (pin "2") (pinfunction "2_2") (pintype "passive"))
      (node (ref "R49") (pin "2") (pinfunction "2_2") (pintype "passive"))
      (node (ref "U1") (pin "13") (pinfunction "GPIO10_13") (pintype "bidirectional"))
    )
    (net (code "25") (name "GND") (class "Default")
      (node (ref "BOOT") (pin "1") (pinfunction "1_1") (pintype "bidirectional"))
      (node (ref "C1") (pin "2") (pinfunction "2_2") (pintype "passive"))
      (node (ref "C10") (pin "2") (pinfunction "2_2") (pintype "passive"))
      (node (ref "C11") (pin "2") (pinfunction "2_2") (pintype "passive"))
      (node (ref "C12") (pin "2") (pinfunction "2_2") (pintype "passive"))
      (node (ref "C13") (pin "2") (pinfunction "2_2") (pintype "passive"))
      (node (ref "C14") (pin "2") (pinfunction "2_2") (pintype "passive"))
      (node (ref "C15") (pin "2") (pinfunction "2_2") (pintype "passive"))
      (node (ref "C16") (pin "2") (pinfunction "2_2") (pintype "passive"))
      (node (ref "C17") (pin "2") (pinfunction "2_2") (pintype "passive"))
      (node (ref "C18") (pin "2") (pinfunction "2_2") (pintype "passive"))
      (node (ref "C19") (pin "2") (pinfunction "2_2") (pintype "passive"))
      (node (ref "C2") (pin "1") (pinfunction "1_1") (pintype "passive"))
      (node (ref "C21") (pin "2") (pinfunction "2_2") (pintype "passive"))
      (node (ref "C22") (pin "2") (pinfunction "2_2") (pintype "passive"))
      (node (ref "C24") (pin "2") (pinfunction "2_2") (pintype "passive"))
      (node (ref "C25") (pin "1") (pinfunction "1_1") (pintype "passive"))
      (node (ref "C26") (pin "2") (pinfunction "2_2") (pintype "passive"))
      (node (ref "C27") (pin "2") (pinfunction "2_2") (pintype "passive"))
      (node (ref "C3") (pin "2") (pinfunction "2_2") (pintype "passive"))
      (node (ref "C30") (pin "1") (pinfunction "1_1") (pintype "passive"))
      (node (ref "C31") (pin "1") (pinfunction "1_1") (pintype "passive"))
      (node (ref "C32") (pin "1") (pinfunction "1_1") (pintype "passive"))
      (node (ref "C33") (pin "-") (pinfunction "-_-") (pintype "passive"))
      (node (ref "C34") (pin "2") (pinfunction "2_2") (pintype "passive"))
      (node (ref "C38") (pin "2") (pinfunction "2_2") (pintype "passive"))
      (node (ref "C39") (pin "2") (pinfunction "2_2") (pintype "passive"))
      (node (ref "C4") (pin "2") (pinfunction "2_2") (pintype "passive"))
      (node (ref "C40") (pin "2") (pinfunction "2_2") (pintype "passive"))
      (node (ref "C42") (pin "2") (pinfunction "2_2") (pintype "passive"))
      (node (ref "C43") (pin "2") (pinfunction "2_2") (pintype "passive"))
      (node (ref "C44") (pin "2") (pinfunction "2_2") (pintype "passive"))
      (node (ref "C45") (pin "2") (pinfunction "2_2") (pintype "passive"))
      (node (ref "C5") (pin "2") (pinfunction "2_2") (pintype "passive"))
      (node (ref "C6") (pin "2") (pinfunction "2_2") (pintype "passive"))
      (node (ref "C7") (pin "2") (pinfunction "2_2") (pintype "passive"))
      (node (ref "C8") (pin "2") (pinfunction "2_2") (pintype "passive"))
      (node (ref "C9") (pin "2") (pinfunction "2_2") (pintype "passive"))
      (node (ref "D2") (pin "2") (pinfunction "GND_2") (pintype "power_in"))
      (node (ref "D3") (pin "C") (pinfunction "C_C") (pintype "passive"))
      (node (ref "D4") (pin "1") (pinfunction "1_1") (pintype "passive"))
      (node (ref "D6") (pin "1") (pinfunction "1_1") (pintype "passive"))
      (node (ref "D7") (pin "1") (pinfunction "1_1") (pintype "passive"))
      (node (ref "D8") (pin "1") (pinfunction "1_1") (pintype "passive"))
      (node (ref "D9") (pin "K") (pinfunction "C_K") (pintype "passive"))
      (node (ref "ENDSTOP") (pin "1") (pinfunction "S_1") (pintype "passive"))
      (node (ref "GND") (pin "P$1") (pinfunction "1_P$1") (pintype "bidirectional"))
      (node (ref "J1") (pin "2") (pinfunction "2_2") (pintype "passive"))
      (node (ref "J3") (pin "3") (pinfunction "3_3") (pintype "passive"))
      (node (ref "M1") (pin "P$1") (pinfunction "S_P$1") (pintype "passive"))
      (node (ref "M1") (pin "P$2") (pinfunction "S_P$2") (pintype "passive"))
      (node (ref "M1") (pin "P$3") (pinfunction "S_P$3") (pintype "passive"))
      (node (ref "M2") (pin "2") (pinfunction "S_2") (pintype "passive"))
      (node (ref "M3") (pin "2") (pinfunction "S_2") (pintype "passive"))
      (node (ref "M4") (pin "2") (pinfunction "S_2") (pintype "passive"))
      (node (ref "P1") (pin "1") (pinfunction "GND_1") (pintype "bidirectional"))
      (node (ref "P2") (pin "2") (pinfunction "GND_2") (pintype "input"))
      (node (ref "R22") (pin "1") (pinfunction "1_1") (pintype "passive"))
      (node (ref "R26") (pin "1") (pinfunction "1_1") (pintype "passive"))
      (node (ref "R27") (pin "1") (pinfunction "1_1") (pintype "passive"))
      (node (ref "R30") (pin "1") (pinfunction "1_1") (pintype "passive"))
      (node (ref "R37") (pin "1") (pinfunction "1_1") (pintype "passive"))
      (node (ref "R45") (pin "1") (pinfunction "1_1") (pintype "passive"))
      (node (ref "R47") (pin "1") (pinfunction "1_1") (pintype "passive"))
      (node (ref "R49") (pin "1") (pinfunction "1_1") (pintype "passive"))
      (node (ref "R6") (pin "1") (pinfunction "1_1") (pintype "passive"))
      (node (ref "R9") (pin "1") (pinfunction "1_1") (pintype "passive"))
      (node (ref "RST") (pin "1") (pinfunction "1_1") (pintype "bidirectional"))
      (node (ref "U1") (pin "19") (pinfunction "TESTEN_19") (pintype "passive"))
      (node (ref "U1") (pin "57") (pinfunction "GND_57") (pintype "passive"))
      (node (ref "U2") (pin "4") (pinfunction "GND_4") (pintype "passive"))
      (node (ref "U3") (pin "2") (pinfunction "GND_2") (pintype "power_in"))
      (node (ref "U3") (pin "8") (pinfunction "STBY_8") (pintype "input"))
      (node (ref "U5") (pin "2") (pinfunction "GND_2") (pintype "bidirectional"))
      (node (ref "U5") (pin "4") (pinfunction "GND1_4") (pintype "bidirectional"))
      (node (ref "U5") (pin "5") (pinfunction "GND2_5") (pintype "bidirectional"))
      (node (ref "U6") (pin "3") (pinfunction "GND_3") (pintype "power_in"))
      (node (ref "U7") (pin "13") (pinfunction "CLK_13") (pintype "input"))
      (node (ref "U7") (pin "18") (pinfunction "GND_18") (pintype "power_in"))
      (node (ref "U7") (pin "29") (pinfunction "EPAD_29") (pintype "passive"))
      (node (ref "U7") (pin "3") (pinfunction "GND_2_3") (pintype "power_in"))
      (node (ref "U7") (pin "7") (pinfunction "SPREAD_7") (pintype "input"))
      (node (ref "USB") (pin "1") (pinfunction "GND_1") (pintype "power_in"))
      (node (ref "USB") (pin "12") (pinfunction "GND2_12") (pintype "power_in"))
      (node (ref "USB") (pin "13") (pinfunction "SHLD_13") (pintype "passive"))
      (node (ref "USB") (pin "14") (pinfunction "SHLD_14") (pintype "passive"))
      (node (ref "USB") (pin "15") (pinfunction "SHLD_15") (pintype "passive"))
      (node (ref "USB") (pin "16") (pinfunction "SHLD_16") (pintype "passive"))
      (node (ref "USB") (pin "18") (pinfunction "SHLD_18") (pintype "passive"))
      (node (ref "USB") (pin "19") (pinfunction "SHLD_19") (pintype "passive"))
      (node (ref "USB") (pin "20") (pinfunction "SHLD_20") (pintype "passive"))
      (node (ref "USB") (pin "21") (pinfunction "SHLD_21") (pintype "passive"))
      (node (ref "USB") (pin "24") (pinfunction "SHLD_24") (pintype "passive"))
      (node (ref "USB") (pin "25") (pinfunction "SHLD_25") (pintype "passive"))
      (node (ref "USB") (pin "26") (pinfunction "SHLD_26") (pintype "passive"))
      (node (ref "USB") (pin "27") (pinfunction "SHLD_27") (pintype "passive"))
      (node (ref "USB") (pin "28") (pinfunction "SHLD_28") (pintype "passive"))
      (node (ref "USB") (pin "29") (pinfunction "SHLD_29") (pintype "passive"))
      (node (ref "USB") (pin "37") (pinfunction "SHLD_37") (pintype "passive"))
      (node (ref "USB") (pin "39") (pinfunction "SHLD_39") (pintype "passive"))
      (node (ref "USB") (pin "41") (pinfunction "SHLD_41") (pintype "passive"))
      (node (ref "USB") (pin "43") (pinfunction "SHLD_43") (pintype "passive"))
      (node (ref "X1") (pin "P$2") (pinfunction "GND_P$2") (pintype "bidirectional"))
      (node (ref "X1") (pin "P$4") (pinfunction "GND_P$4") (pintype "bidirectional"))
    )
    (net (code "26") (name "HE0") (class "Default")
      (node (ref "HE0") (pin "P$1") (pinfunction "1_P$1") (pintype "bidirectional"))
      (node (ref "R37") (pin "2") (pinfunction "2_2") (pintype "passive"))
      (node (ref "U1") (pin "31") (pinfunction "GPIO20_31") (pintype "bidirectional"))
      (node (ref "U6") (pin "2") (pinfunction "A_2") (pintype "input"))
    )
    (net (code "27") (name "HE0_PWR") (class "Default")
      (node (ref "J3") (pin "1") (pinfunction "1_1") (pintype "passive"))
      (node (ref "M1") (pin "P$5") (pinfunction "D_P$5") (pintype "passive"))
      (node (ref "M1") (pin "P$6") (pinfunction "D_P$6") (pintype "passive"))
      (node (ref "M1") (pin "P$7") (pinfunction "D_P$7") (pintype "passive"))
      (node (ref "M1") (pin "P$8") (pinfunction "D_P$8") (pintype "passive"))
      (node (ref "M1") (pin "P$9") (pinfunction "D_P$9") (pintype "passive"))
    )
    (net (code "28") (name "I2C_SCL") (class "Default")
      (node (ref "U1") (pin "35") (pinfunction "GPIO23_35") (pintype "bidirectional"))
    )
    (net (code "29") (name "I2C_SDA") (class "Default")
      (node (ref "U1") (pin "34") (pinfunction "GPIO22_34") (pintype "bidirectional"))
    )
    (net (code "30") (name "Net-(BOOT-Pad2)") (class "Default")
      (node (ref "BOOT") (pin "2") (pinfunction "2_2") (pintype "bidirectional"))
      (node (ref "R12") (pin "2") (pinfunction "2_2") (pintype "passive"))
    )
    (net (code "31") (name "Net-(C23-Pad1)") (class "Default")
      (node (ref "C23") (pin "1") (pinfunction "1_1") (pintype "passive"))
      (node (ref "R7") (pin "1") (pinfunction "1_1") (pintype "passive"))
      (node (ref "R8") (pin "2") (pinfunction "2_2") (pintype "passive"))
    )
    (net (code "32") (name "Net-(C_FAN2B-S)") (class "Default")
      (node (ref "C_FAN") (pin "2") (pinfunction "S_2") (pintype "passive"))
      (node (ref "C_FAN2") (pin "2") (pinfunction "S_2") (pintype "passive"))
      (node (ref "M4") (pin "3") (pinfunction "D_3") (pintype "passive"))
    )
    (net (code "33") (name "Net-(D1-A)") (class "Default")
      (node (ref "D1") (pin "2") (pinfunction "A_2") (pintype "passive"))
      (node (ref "F1") (pin "1") (pinfunction "1_1") (pintype "passive"))
    )
    (net (code "34") (name "Net-(D2-I{slash}O1)") (class "Default")
      (node (ref "D2") (pin "1") (pinfunction "I/O1_2_1") (pintype "bidirectional"))
      (node (ref "D2") (pin "6") (pinfunction "I/O1_6") (pintype "bidirectional"))
      (node (ref "IO2") (pin "P$1") (pinfunction "1_P$1") (pintype "bidirectional"))
      (node (ref "R10") (pin "1") (pinfunction "1_1") (pintype "passive"))
      (node (ref "USB") (pin "6") (pinfunction "AD+_6") (pintype "passive"))
      (node (ref "USB") (pin "8") (pinfunction "BD+_8") (pintype "passive"))
    )
    (net (code "35") (name "Net-(D2-I{slash}O2)") (class "Default")
      (node (ref "D2") (pin "3") (pinfunction "I/O2_2_3") (pintype "bidirectional"))
      (node (ref "D2") (pin "4") (pinfunction "I/O2_4") (pintype "bidirectional"))
      (node (ref "IO1") (pin "P$1") (pinfunction "1_P$1") (pintype "bidirectional"))
      (node (ref "R11") (pin "1") (pinfunction "1_1") (pintype "passive"))
      (node (ref "USB") (pin "5") (pinfunction "BD-_5") (pintype "passive"))
      (node (ref "USB") (pin "7") (pinfunction "AD-_7") (pintype "passive"))
    )
    (net (code "36") (name "Net-(D2-VBUS)") (class "Default")
      (node (ref "D2") (pin "5") (pinfunction "VBUS_5") (pintype "power_in"))
      (node (ref "F1") (pin "2") (pinfunction "2_2") (pintype "passive"))
      (node (ref "SJ3") (pin "1") (pinfunction "1_1") (pintype "passive"))
    )
    (net (code "37") (name "Net-(D3-PadA)") (class "Default")
      (node (ref "D3") (pin "A") (pinfunction "A_A") (pintype "passive"))
      (node (ref "R15") (pin "1") (pinfunction "1_1") (pintype "passive"))
    )
    (net (code "38") (name "Net-(D4-Pad3)") (class "Default")
      (node (ref "D4") (pin "3") (pinfunction "3_3") (pintype "passive"))
      (node (ref "R35") (pin "2") (pinfunction "2_2") (pintype "passive"))
      (node (ref "R36") (pin "1") (pinfunction "1_1") (pintype "passive"))
    )
    (net (code "39") (name "Net-(D9-PadA)") (class "Default")
      (node (ref "D9") (pin "A") (pinfunction "A_A") (pintype "passive"))
      (node (ref "R28") (pin "1") (pinfunction "1_1") (pintype "passive"))
    )
    (net (code "40") (name "Net-(ENDSTOPB-S)") (class "Default")
      (node (ref "ENDSTOP") (pin "2") (pinfunction "S_2") (pintype "passive"))
      (node (ref "R40") (pin "2") (pinfunction "2_2") (pintype "passive"))
      (node (ref "R41") (pin "2") (pinfunction "2_2") (pintype "passive"))
    )
    (net (code "41") (name "Net-(H_FANB-S)") (class "Default")
      (node (ref "H_FAN") (pin "2") (pinfunction "S_2") (pintype "passive"))
      (node (ref "M2") (pin "3") (pinfunction "D_3") (pintype "passive"))
    )
    (net (code "42") (name "Net-(J3-Pad4)") (class "Default")
      (node (ref "J3") (pin "4") (pinfunction "4_4") (pintype "passive"))
      (node (ref "R33") (pin "1") (pinfunction "1_1") (pintype "passive"))
      (node (ref "R34") (pin "1") (pinfunction "1_1") (pintype "passive"))
      (node (ref "R35") (pin "1") (pinfunction "1_1") (pintype "passive"))
    )
    (net (code "43") (name "Net-(M1-G)") (class "Default")
      (node (ref "M1") (pin "P$4") (pinfunction "G_P$4") (pintype "passive"))
      (node (ref "R31") (pin "1") (pinfunction "1_1") (pintype "passive"))
    )
    (net (code "44") (name "Net-(M2-G)") (class "Default")
      (node (ref "D6") (pin "3") (pinfunction "3_3") (pintype "passive"))
      (node (ref "M2") (pin "1") (pinfunction "G_1") (pintype "passive"))
      (node (ref "R44") (pin "1") (pinfunction "1_1") (pintype "passive"))
    )
    (net (code "45") (name "Net-(M3-D)") (class "Default")
      (node (ref "M3") (pin "3") (pinfunction "D_3") (pintype "passive"))
      (node (ref "M_FAN") (pin "2") (pinfunction "S_2") (pintype "passive"))
    )
    (net (code "46") (name "Net-(M3-G)") (class "Default")
      (node (ref "D7") (pin "3") (pinfunction "3_3") (pintype "passive"))
      (node (ref "M3") (pin "1") (pinfunction "G_1") (pintype "passive"))
      (node (ref "R46") (pin "1") (pinfunction "1_1") (pintype "passive"))
    )
    (net (code "47") (name "Net-(M4-G)") (class "Default")
      (node (ref "D8") (pin "3") (pinfunction "3_3") (pintype "passive"))
      (node (ref "M4") (pin "1") (pinfunction "G_1") (pintype "passive"))
      (node (ref "R48") (pin "1") (pinfunction "1_1") (pintype "passive"))
    )
    (net (code "48") (name "Net-(P1-BOOT)") (class "Default")
      (node (ref "C20") (pin "1") (pinfunction "1_1") (pintype "passive"))
      (node (ref "P1") (pin "6") (pinfunction "BOOT_6") (pintype "bidirectional"))
    )
    (net (code "49") (name "Net-(P1-EN)") (class "Default")
      (node (ref "P1") (pin "5") (pinfunction "EN_5") (pintype "bidirectional"))
      (node (ref "R5") (pin "1") (pinfunction "1_1") (pintype "passive"))
      (node (ref "R6") (pin "2") (pinfunction "2_2") (pintype "passive"))
    )
    (net (code "50") (name "Net-(P1-FB)") (class "Default")
      (node (ref "C23") (pin "2") (pinfunction "2_2") (pintype "passive"))
      (node (ref "P1") (pin "4") (pinfunction "FB_4") (pintype "bidirectional"))
      (node (ref "R8") (pin "1") (pinfunction "1_1") (pintype "passive"))
      (node (ref "R9") (pin "2") (pinfunction "2_2") (pintype "passive"))
    )
    (net (code "51") (name "Net-(P1-SW)") (class "Default")
      (node (ref "C20") (pin "2") (pinfunction "2_2") (pintype "passive"))
      (node (ref "P1") (pin "2") (pinfunction "SW_2") (pintype "bidirectional"))
      (node (ref "U$1") (pin "1") (pinfunction "1_1") (pintype "bidirectional"))
    )
    (net (code "52") (name "Net-(R1-Pad1)") (class "Default")
      (node (ref "R1") (pin "1") (pinfunction "1_1") (pintype "passive"))
      (node (ref "R2") (pin "2") (pinfunction "2_2") (pintype "passive"))
    )
    (net (code "53") (name "Net-(R16-Pad2)") (class "Default")
      (node (ref "R16") (pin "2") (pinfunction "2_2") (pintype "passive"))
      (node (ref "SJ1") (pin "2") (pinfunction "2_2") (pintype "passive"))
    )
    (net (code "54") (name "Net-(R34-Pad2)") (class "Default")
      (node (ref "R34") (pin "2") (pinfunction "2_2") (pintype "passive"))
      (node (ref "SJ2") (pin "1") (pinfunction "1_1") (pintype "passive"))
    )
    (net (code "55") (name "Net-(U1-GPIO2)") (class "Default")
      (node (ref "R28") (pin "2") (pinfunction "2_2") (pintype "passive"))
      (node (ref "U1") (pin "4") (pinfunction "GPIO2_4") (pintype "bidirectional"))
    )
    (net (code "56") (name "Net-(U3-CANH)") (class "Default")
      (node (ref "U$4") (pin "1") (pinfunction "1_1") (pintype "passive"))
      (node (ref "U3") (pin "7") (pinfunction "CANH_7") (pintype "output"))
    )
    (net (code "57") (name "Net-(U3-CANL)") (class "Default")
      (node (ref "U$4") (pin "2") (pinfunction "2_2") (pintype "passive"))
      (node (ref "U3") (pin "6") (pinfunction "CANL_6") (pintype "output"))
    )
    (net (code "58") (name "Net-(U6-Y)") (class "Default")
      (node (ref "R30") (pin "2") (pinfunction "2_2") (pintype "passive"))
      (node (ref "R31") (pin "2") (pinfunction "2_2") (pintype "passive"))
      (node (ref "U6") (pin "4") (pinfunction "Y_4") (pintype "output"))
    )
    (net (code "59") (name "Net-(U7-5VOUT)") (class "Default")
      (node (ref "C32") (pin "2") (pinfunction "2_2") (pintype "passive"))
      (node (ref "U7") (pin "8") (pinfunction "5VOUT_8") (pintype "output"))
    )
    (net (code "60") (name "Net-(U7-CPI)") (class "Default")
      (node (ref "C28") (pin "1") (pinfunction "1_1") (pintype "passive"))
      (node (ref "U7") (pin "5") (pinfunction "CPI_5") (pintype "input"))
    )
    (net (code "61") (name "Net-(U7-CPO)") (class "Default")
      (node (ref "C28") (pin "2") (pinfunction "2_2") (pintype "passive"))
      (node (ref "U7") (pin "4") (pinfunction "CPO_4") (pintype "output"))
    )
    (net (code "62") (name "Net-(U7-DIR)") (class "Default")
      (node (ref "R25") (pin "2") (pinfunction "2_2") (pintype "passive"))
      (node (ref "U7") (pin "19") (pinfunction "DIR_19") (pintype "input"))
    )
    (net (code "63") (name "Net-(U7-ENN)") (class "Default")
      (node (ref "R21") (pin "2") (pinfunction "2_2") (pintype "passive"))
      (node (ref "R23") (pin "1") (pinfunction "1_1") (pintype "passive"))
      (node (ref "U7") (pin "2") (pinfunction "ENN_2") (pintype "input"))
    )
    (net (code "64") (name "Net-(U7-STEP)") (class "Default")
      (node (ref "R24") (pin "2") (pinfunction "2_2") (pintype "passive"))
      (node (ref "U7") (pin "16") (pinfunction "STEP_16") (pintype "input"))
    )
    (net (code "65") (name "Net-(U7-VCP)") (class "Default")
      (node (ref "C29") (pin "2") (pinfunction "2_2") (pintype "passive"))
      (node (ref "U7") (pin "6") (pinfunction "VCP_6") (pintype "power_in"))
    )
    (net (code "66") (name "Net-(X1-P2)") (class "Default")
      (node (ref "C2") (pin "2") (pinfunction "2_2") (pintype "passive"))
      (node (ref "R3") (pin "1") (pinfunction "1_1") (pintype "passive"))
      (node (ref "X1") (pin "P$3") (pinfunction "P2_P$3") (pintype "bidirectional"))
    )
    (net (code "67") (name "OSC_IN") (class "Default")
      (node (ref "C1") (pin "1") (pinfunction "1_1") (pintype "passive"))
      (node (ref "R4") (pin "2") (pinfunction "2_2") (pintype "passive"))
      (node (ref "U1") (pin "20") (pinfunction "XIN_20") (pintype "passive"))
      (node (ref "X1") (pin "P$1") (pinfunction "P1_P$1") (pintype "bidirectional"))
    )
    (net (code "68") (name "OSC_OUT") (class "Default")
      (node (ref "R3") (pin "2") (pinfunction "2_2") (pintype "passive"))
      (node (ref "R4") (pin "1") (pinfunction "1_1") (pintype "passive"))
      (node (ref "U1") (pin "21") (pinfunction "XOUT_21") (pintype "output"))
    )
    (net (code "69") (name "QSPI_SCK") (class "Default")
      (node (ref "U1") (pin "52") (pinfunction "QSPI_SCLK_52") (pintype "passive"))
      (node (ref "U2") (pin "6") (pinfunction "CLK_6") (pintype "passive"))
    )
    (net (code "70") (name "QSPI_SD0") (class "Default")
      (node (ref "U1") (pin "53") (pinfunction "QSPI_SD0_53") (pintype "bidirectional"))
      (node (ref "U2") (pin "5") (pinfunction "DI_(IO0)_5") (pintype "passive"))
    )
    (net (code "71") (name "QSPI_SD1") (class "Default")
      (node (ref "U1") (pin "55") (pinfunction "QSPI_SD1_55") (pintype "bidirectional"))
      (node (ref "U2") (pin "2") (pinfunction "DO_(IO1)_2") (pintype "passive"))
    )
    (net (code "72") (name "QSPI_SD2") (class "Default")
      (node (ref "U1") (pin "54") (pinfunction "QSPI_SD2_54") (pintype "bidirectional"))
      (node (ref "U2") (pin "3") (pinfunction "/WP_(IO2)_3") (pintype "passive"))
    )
    (net (code "73") (name "QSPI_SD3") (class "Default")
      (node (ref "U1") (pin "51") (pinfunction "QSPI_SD3_51") (pintype "bidirectional"))
      (node (ref "U2") (pin "7") (pinfunction "/RESET_(IO3)_7") (pintype "passive"))
    )
    (net (code "74") (name "QSPI_SS") (class "Default")
      (node (ref "R12") (pin "1") (pinfunction "1_1") (pintype "passive"))
      (node (ref "R13") (pin "1") (pinfunction "1_1") (pintype "passive"))
      (node (ref "U1") (pin "56") (pinfunction "QSPI_SS_N_56") (pintype "passive"))
      (node (ref "U2") (pin "1") (pinfunction "/CS_1") (pintype "passive"))
    )
    (net (code "75") (name "RESET") (class "Default")
      (node (ref "C25") (pin "2") (pinfunction "2_2") (pintype "passive"))
      (node (ref "R14") (pin "1") (pinfunction "1_1") (pintype "passive"))
      (node (ref "RST") (pin "2") (pinfunction "2_2") (pintype "bidirectional"))
      (node (ref "U1") (pin "26") (pinfunction "RUN_26") (pintype "passive"))
    )
    (net (code "76") (name "SPI0_CS") (class "Default")
      (node (ref "U1") (pin "28") (pinfunction "GPIO17_28") (pintype "bidirectional"))
    )
    (net (code "77") (name "SPI0_MISO") (class "Default")
      (node (ref "U1") (pin "27") (pinfunction "GPIO16_27") (pintype "bidirectional"))
    )
    (net (code "78") (name "SPI0_MOSI") (class "Default")
      (node (ref "U1") (pin "30") (pinfunction "GPIO19_30") (pintype "bidirectional"))
    )
    (net (code "79") (name "SPI0_SCK") (class "Default")
      (node (ref "U1") (pin "29") (pinfunction "GPIO18_29") (pintype "bidirectional"))
    )
    (net (code "80") (name "SPI1_CS") (class "Default")
      (node (ref "R19") (pin "1") (pinfunction "1_1") (pintype "passive"))
      (node (ref "U1") (pin "16") (pinfunction "GPIO13_16") (pintype "bidirectional"))
      (node (ref "U5") (pin "7") (pinfunction "~{CS}_7") (pintype "bidirectional"))
    )
    (net (code "81") (name "SPI1_MISO") (class "Default")
      (node (ref "R18") (pin "1") (pinfunction "1_1") (pintype "passive"))
      (node (ref "U1") (pin "15") (pinfunction "GPIO12_15") (pintype "bidirectional"))
      (node (ref "U5") (pin "12") (pinfunction "SDO/ALT_ADDRESS_12") (pintype "bidirectional"))
    )
    (net (code "82") (name "SPI1_MOSI") (class "Default")
      (node (ref "R17") (pin "1") (pinfunction "1_1") (pintype "passive"))
      (node (ref "U1") (pin "18") (pinfunction "GPIO15_18") (pintype "bidirectional"))
      (node (ref "U5") (pin "13") (pinfunction "SDA/SDI/SDIO_13") (pintype "bidirectional"))
    )
    (net (code "83") (name "SPI1_SCK") (class "Default")
      (node (ref "R20") (pin "1") (pinfunction "1_1") (pintype "passive"))
      (node (ref "U1") (pin "17") (pinfunction "GPIO14_17") (pintype "bidirectional"))
      (node (ref "U5") (pin "14") (pinfunction "SCL/SCLK_14") (pintype "bidirectional"))
    )
    (net (code "84") (name "SWCLK") (class "Default")
      (node (ref "U1") (pin "24") (pinfunction "SWCLK_24") (pintype "passive"))
    )
    (net (code "85") (name "SWDIO") (class "Default")
      (node (ref "U1") (pin "25") (pinfunction "SWDIO_25") (pintype "passive"))
    )
    (net (code "86") (name "TH0") (class "Default")
      (node (ref "C40") (pin "1") (pinfunction "1_1") (pintype "passive"))
      (node (ref "R36") (pin "2") (pinfunction "2_2") (pintype "passive"))
      (node (ref "TH0") (pin "P$1") (pinfunction "1_P$1") (pintype "bidirectional"))
      (node (ref "U1") (pin "38") (pinfunction "GPIO26/ADC0_38") (pintype "bidirectional"))
    )
    (net (code "87") (name "USB_N") (class "Default")
      (node (ref "R11") (pin "2") (pinfunction "2_2") (pintype "passive"))
      (node (ref "U1") (pin "46") (pinfunction "USB_DM_46") (pintype "passive"))
    )
    (net (code "88") (name "USB_P") (class "Default")
      (node (ref "R10") (pin "2") (pinfunction "2_2") (pintype "passive"))
      (node (ref "U1") (pin "47") (pinfunction "USB_DP_47") (pintype "passive"))
    )
    (net (code "89") (name "VBUS") (class "Default")
      (node (ref "SJ3") (pin "2") (pinfunction "2_2") (pintype "passive"))
      (node (ref "USB") (pin "11") (pinfunction "VBUS2_11") (pintype "power_in"))
      (node (ref "USB") (pin "2") (pinfunction "VBUS_2") (pintype "power_in"))
    )
    (net (code "90") (name "unconnected-(P2-NC-Pad4)") (class "Default")
      (node (ref "P2") (pin "4") (pinfunction "NC_4") (pintype "no_connect"))
    )
    (net (code "91") (name "unconnected-(U1-GPIO3-Pad5)") (class "Default")
      (node (ref "U1") (pin "5") (pinfunction "GPIO3_5") (pintype "bidirectional"))
    )
    (net (code "92") (name "unconnected-(U1-GPIO4-Pad6)") (class "Default")
      (node (ref "U1") (pin "6") (pinfunction "GPIO4_6") (pintype "bidirectional"))
    )
    (net (code "93") (name "unconnected-(U1-GPIO5-Pad7)") (class "Default")
      (node (ref "U1") (pin "7") (pinfunction "GPIO5_7") (pintype "bidirectional"))
    )
    (net (code "94") (name "unconnected-(U1-GPIO6-Pad8)") (class "Default")
      (node (ref "U1") (pin "8") (pinfunction "GPIO6_8") (pintype "bidirectional"))
    )
    (net (code "95") (name "unconnected-(U1-GPIO11-Pad14)") (class "Default")
      (node (ref "U1") (pin "14") (pinfunction "GPIO11_14") (pintype "bidirectional"))
    )
    (net (code "96") (name "unconnected-(U1-GPIO29{slash}ADC3-Pad41)") (class "Default")
      (node (ref "U1") (pin "41") (pinfunction "GPIO29/ADC3_41") (pintype "bidirectional"))
    )
    (net (code "97") (name "unconnected-(U5-INT1-Pad8)") (class "Default")
      (node (ref "U5") (pin "8") (pinfunction "INT1_8") (pintype "bidirectional"))
    )
    (net (code "98") (name "unconnected-(U5-INT2-Pad9)") (class "Default")
      (node (ref "U5") (pin "9") (pinfunction "INT2_9") (pintype "bidirectional"))
    )
    (net (code "99") (name "unconnected-(U5-NC-Pad10)") (class "Default")
      (node (ref "U5") (pin "10") (pinfunction "NC_10") (pintype "bidirectional"))
    )
    (net (code "100") (name "unconnected-(U5-RESERVED-Pad3)") (class "Default")
      (node (ref "U5") (pin "3") (pinfunction "RESERVED_3") (pintype "bidirectional"))
    )
    (net (code "101") (name "unconnected-(U5-RESERVED1-Pad11)") (class "Default")
      (node (ref "U5") (pin "11") (pinfunction "RESERVED1_11") (pintype "bidirectional"))
    )
    (net (code "102") (name "unconnected-(U6-NC-Pad1)") (class "Default")
      (node (ref "U6") (pin "1") (pinfunction "NC_1") (pintype "passive"))
    )
    (net (code "103") (name "unconnected-(U7-INDEX-Pad12)") (class "Default")
      (node (ref "U7") (pin "12") (pinfunction "INDEX_12") (pintype "output"))
    )
    (net (code "104") (name "unconnected-(U7-MS1_AD0-Pad9)") (class "Default")
      (node (ref "U7") (pin "9") (pinfunction "MS1_AD0_9") (pintype "input"))
    )
    (net (code "105") (name "unconnected-(U7-MS2_AD1-Pad10)") (class "Default")
      (node (ref "U7") (pin "10") (pinfunction "MS2_AD1_10") (pintype "input"))
    )
    (net (code "106") (name "unconnected-(U7-NC-Pad25)") (class "Default")
      (node (ref "U7") (pin "25") (pinfunction "NC_25") (pintype "no_connect"))
    )
    (net (code "107") (name "unconnected-(U7-STDBY-Pad20)") (class "Default")
      (node (ref "U7") (pin "20") (pinfunction "STDBY_20") (pintype "input"))
    )
    (net (code "108") (name "unconnected-(U7-VREF-Pad17)") (class "Default")
      (node (ref "U7") (pin "17") (pinfunction "VREF_17") (pintype "input"))
    )
    (net (code "109") (name "unconnected-(USB-CC1-Pad3)") (class "Default")
      (node (ref "USB") (pin "3") (pinfunction "CC1_3") (pintype "passive"))
    )
    (net (code "110") (name "unconnected-(USB-CC2-Pad9)") (class "Default")
      (node (ref "USB") (pin "9") (pinfunction "CC2_9") (pintype "passive"))
    )
    (net (code "111") (name "unconnected-(USB-SBU1-Pad10)") (class "Default")
      (node (ref "USB") (pin "10") (pinfunction "SBU1_10") (pintype "passive"))
    )
    (net (code "112") (name "unconnected-(USB-SBU2-Pad4)") (class "Default")
      (node (ref "USB") (pin "4") (pinfunction "SBU2_4") (pintype "passive"))
    )
  )
)
